# UWB_F3_CAN_UWB_layout_R2.net
KiCad netlist of a schematic drawn in Altium Designer
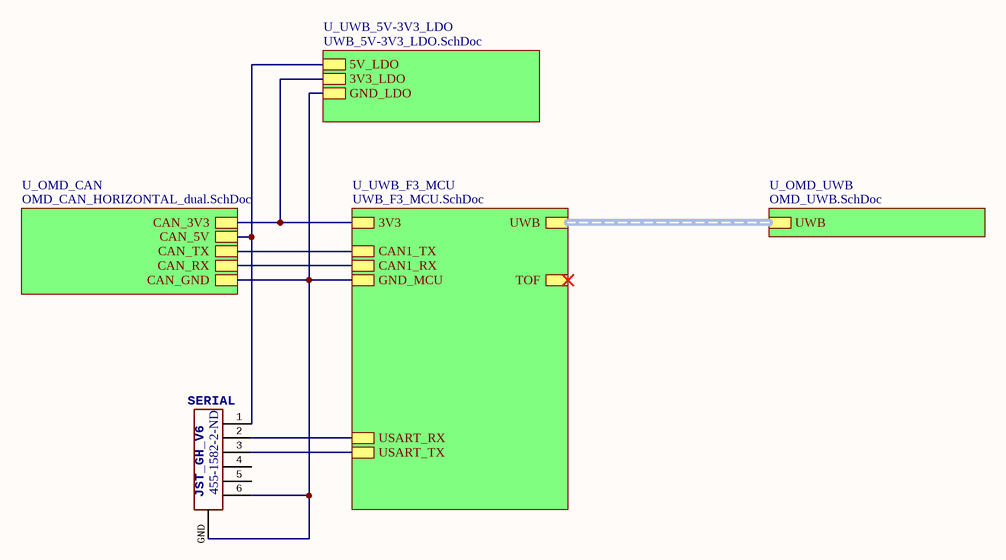
[diagram p0: UWB_F3_CAN_UWB_layout_R2.SchDoc]

(export (version "E")
  (design (tool "Eeschema 10.0.6"))
  (components
    (comp (ref "SERIAL")
      (value "JST_GH_V6")
      (footprint "JST_GH_V6")
      (description "BM06B-GHS-TBT")
      (fields (field (name "SUPPLIER PART NUMBER 1") "455-1582-2-ND"))
      (libsource (lib "CB_SCI_AERO") (part "JST_GH_V6"))
    )
  )
  (nets
    (net (code "2") (name "/5V_LDO") (class "Default")
      (node (ref "SERIAL") (pin "1") (pinfunction "1_1") (pintype "passive"))
    )
    (net (code "5") (name "/CAN_GND") (class "Default")
      (node (ref "SERIAL") (pin "6") (pinfunction "6_6") (pintype "passive"))
      (node (ref "SERIAL") (pin "GND") (pinfunction "GND_GND") (pintype "passive"))
    )
    (net (code "7") (name "/USART_RX") (class "Default")
      (node (ref "SERIAL") (pin "2") (pinfunction "2_2") (pintype "passive"))
    )
    (net (code "8") (name "/USART_TX") (class "Default")
      (node (ref "SERIAL") (pin "3") (pinfunction "3_3") (pintype "passive"))
    )
    (net (code "10") (name "unconnected-(SERIAL-Pad4)") (class "Default")
      (node (ref "SERIAL") (pin "4") (pinfunction "4_4") (pintype "passive"))
    )
    (net (code "11") (name "unconnected-(SERIAL-Pad5)") (class "Default")
      (node (ref "SERIAL") (pin "5") (pinfunction "5_5") (pintype "passive"))
    )
  )
)
